# BLDC_Motor_Driver_mb.net
KiCad netlist of a schematic drawn in EAGLE
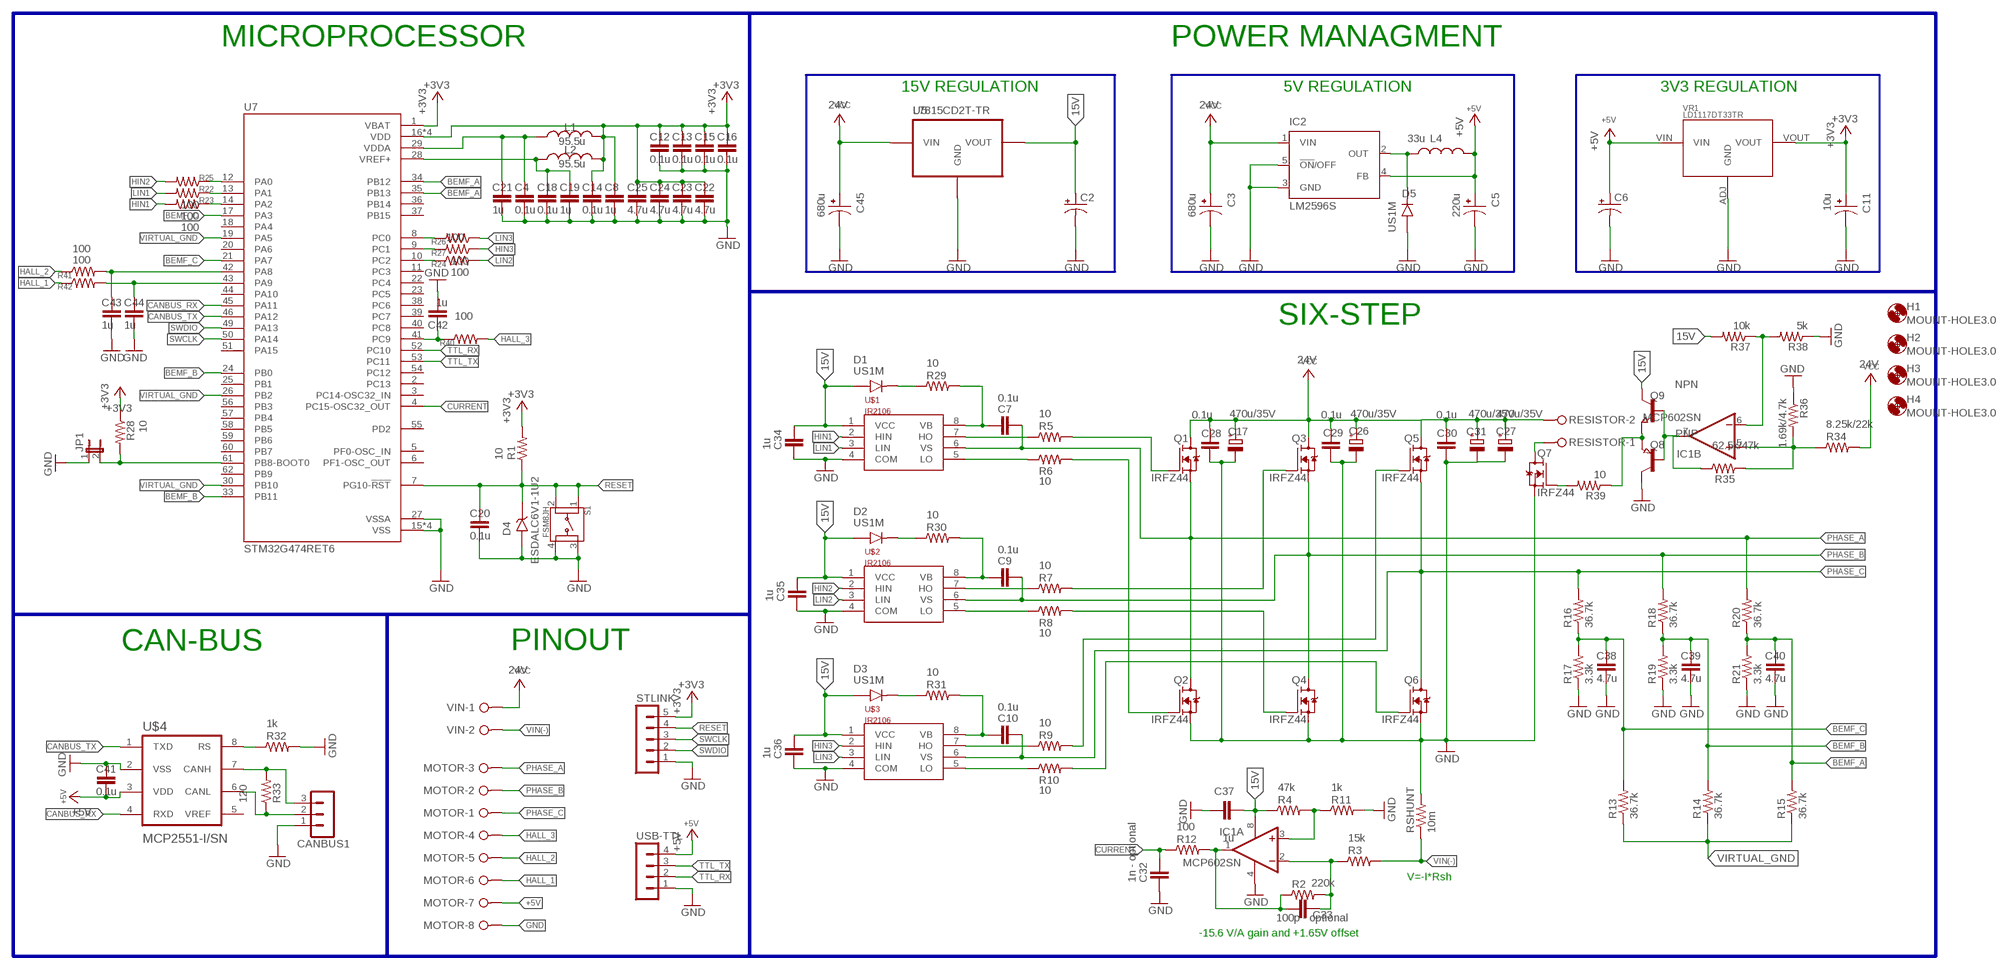
[diagram p0: schematic, sheet 1]

(export (version "E")
  (design (tool "Eeschema 10.0.6"))
  (components
    (comp (ref "C2")
      (value "CPOL-US153CLV-0405")
      (footprint "eagle-import:153CLV-0405")
      (libsource (lib "eagle-import") (part "CPOL-US153CLV-0405"))
    )
    (comp (ref "C3")
      (value "680u")
      (footprint "eagle-import:CAP_EEEFK1H221P")
      (fields (field (name "MF") "Panasonic") (field (name "MP") "EEE-FK1H221P"))
      (libsource (lib "eagle-import") (part "EEEFK1H221P"))
    )
    (comp (ref "C4")
      (value "0.1u")
      (footprint "eagle-import:C1206")
      (libsource (lib "eagle-import") (part "C-EUC1206"))
    )
    (comp (ref "C5")
      (value "220u")
      (footprint "eagle-import:CAP_EEEFK1H221P")
      (fields (field (name "MF") "Panasonic") (field (name "MP") "EEE-FK1H221P"))
      (libsource (lib "eagle-import") (part "EEEFK1H221P"))
    )
    (comp (ref "C6")
      (value "CPOL-US153CLV-0405")
      (footprint "eagle-import:153CLV-0405")
      (libsource (lib "eagle-import") (part "CPOL-US153CLV-0405"))
    )
    (comp (ref "C7")
      (value "0.1u")
      (footprint "eagle-import:C1206")
      (libsource (lib "eagle-import") (part "C-EUC1206"))
    )
    (comp (ref "C8")
      (value "1u")
      (footprint "eagle-import:C1206")
      (libsource (lib "eagle-import") (part "C-EUC1206"))
    )
    (comp (ref "C9")
      (value "0.1u")
      (footprint "eagle-import:C1206")
      (libsource (lib "eagle-import") (part "C-EUC1206"))
    )
    (comp (ref "C10")
      (value "0.1u")
      (footprint "eagle-import:C1206")
      (libsource (lib "eagle-import") (part "C-EUC1206"))
    )
    (comp (ref "C11")
      (value "10u")
      (footprint "eagle-import:CAP_EEEFK1H221P")
      (fields (field (name "MF") "Panasonic") (field (name "MP") "EEE-FK1H221P"))
      (libsource (lib "eagle-import") (part "EEEFK1H221P"))
    )
    (comp (ref "C12")
      (value "0.1u")
      (footprint "eagle-import:C1206")
      (libsource (lib "eagle-import") (part "C-EUC1206"))
    )
    (comp (ref "C13")
      (value "0.1u")
      (footprint "eagle-import:C1206")
      (libsource (lib "eagle-import") (part "C-EUC1206"))
    )
    (comp (ref "C14")
      (value "0.1u")
      (footprint "eagle-import:C1206")
      (libsource (lib "eagle-import") (part "C-EUC1206"))
    )
    (comp (ref "C15")
      (value "0.1u")
      (footprint "eagle-import:C1206")
      (libsource (lib "eagle-import") (part "C-EUC1206"))
    )
    (comp (ref "C16")
      (value "0.1u")
      (footprint "eagle-import:C1206")
      (libsource (lib "eagle-import") (part "C-EUC1206"))
    )
    (comp (ref "C17")
      (value "470u/35V")
      (footprint "eagle-import:E7,5-16")
      (libsource (lib "eagle-import") (part "CPOL-EUE7.5-16"))
    )
    (comp (ref "C18")
      (value "0.1u")
      (footprint "eagle-import:C1206")
      (libsource (lib "eagle-import") (part "C-EUC1206"))
    )
    (comp (ref "C19")
      (value "1u")
      (footprint "eagle-import:C1206")
      (libsource (lib "eagle-import") (part "C-EUC1206"))
    )
    (comp (ref "C20")
      (value "0.1u")
      (footprint "eagle-import:C1206")
      (libsource (lib "eagle-import") (part "C-EUC1206"))
    )
    (comp (ref "C21")
      (value "1u")
      (footprint "eagle-import:C1206")
      (libsource (lib "eagle-import") (part "C-EUC1206"))
    )
    (comp (ref "C22")
      (value "4.7u")
      (footprint "eagle-import:C1206")
      (libsource (lib "eagle-import") (part "C-EUC1206"))
    )
    (comp (ref "C23")
      (value "4.7u")
      (footprint "eagle-import:C1206")
      (libsource (lib "eagle-import") (part "C-EUC1206"))
    )
    (comp (ref "C24")
      (value "4.7u")
      (footprint "eagle-import:C1206")
      (libsource (lib "eagle-import") (part "C-EUC1206"))
    )
    (comp (ref "C25")
      (value "4.7u")
      (footprint "eagle-import:C1206")
      (libsource (lib "eagle-import") (part "C-EUC1206"))
    )
    (comp (ref "C26")
      (value "470u/35V")
      (footprint "eagle-import:E7,5-16")
      (libsource (lib "eagle-import") (part "CPOL-EUE7.5-16"))
    )
    (comp (ref "C27")
      (value "470u/35V")
      (footprint "eagle-import:E7,5-16")
      (libsource (lib "eagle-import") (part "CPOL-EUE7.5-16"))
    )
    (comp (ref "C28")
      (value "0.1u")
      (footprint "eagle-import:C1206")
      (libsource (lib "eagle-import") (part "C-EUC1206"))
    )
    (comp (ref "C29")
      (value "0.1u")
      (footprint "eagle-import:C1206")
      (libsource (lib "eagle-import") (part "C-EUC1206"))
    )
    (comp (ref "C30")
      (value "0.1u")
      (footprint "eagle-import:C1206")
      (libsource (lib "eagle-import") (part "C-EUC1206"))
    )
    (comp (ref "C31")
      (value "470u/35V")
      (footprint "eagle-import:E7,5-16")
      (libsource (lib "eagle-import") (part "CPOL-EUE7.5-16"))
    )
    (comp (ref "C32")
      (value "1n - optional")
      (footprint "eagle-import:C1206")
      (libsource (lib "eagle-import") (part "C-EUC1206"))
    )
    (comp (ref "C33")
      (value "100p - optional")
      (footprint "eagle-import:C1206")
      (libsource (lib "eagle-import") (part "C-EUC1206"))
    )
    (comp (ref "C34")
      (value "1u")
      (footprint "eagle-import:C1206")
      (libsource (lib "eagle-import") (part "C-EUC1206"))
    )
    (comp (ref "C35")
      (value "1u")
      (footprint "eagle-import:C1206")
      (libsource (lib "eagle-import") (part "C-EUC1206"))
    )
    (comp (ref "C36")
      (value "1u")
      (footprint "eagle-import:C1206")
      (libsource (lib "eagle-import") (part "C-EUC1206"))
    )
    (comp (ref "C37")
      (value "1u")
      (footprint "eagle-import:C1206")
      (libsource (lib "eagle-import") (part "C-EUC1206"))
    )
    (comp (ref "C38")
      (value "4.7u")
      (footprint "eagle-import:C1206")
      (libsource (lib "eagle-import") (part "C-EUC1206"))
    )
    (comp (ref "C39")
      (value "4.7u")
      (footprint "eagle-import:C1206")
      (libsource (lib "eagle-import") (part "C-EUC1206"))
    )
    (comp (ref "C40")
      (value "4.7u")
      (footprint "eagle-import:C1206")
      (libsource (lib "eagle-import") (part "C-EUC1206"))
    )
    (comp (ref "C41")
      (value "0.1u")
      (footprint "eagle-import:C1206")
      (libsource (lib "eagle-import") (part "C-EUC1206"))
    )
    (comp (ref "C42")
      (value "1u")
      (footprint "eagle-import:C1206")
      (libsource (lib "eagle-import") (part "C-EUC1206"))
    )
    (comp (ref "C43")
      (value "1u")
      (footprint "eagle-import:C1206")
      (libsource (lib "eagle-import") (part "C-EUC1206"))
    )
    (comp (ref "C44")
      (value "1u")
      (footprint "eagle-import:C1206")
      (libsource (lib "eagle-import") (part "C-EUC1206"))
    )
    (comp (ref "C45")
      (value "680u")
      (footprint "eagle-import:CAP_EEEFK1H221P")
      (fields (field (name "MF") "Panasonic") (field (name "MP") "EEE-FK1H221P"))
      (libsource (lib "eagle-import") (part "EEEFK1H221P"))
    )
    (comp (ref "CANBUS1")
      (value "MA03-1")
      (footprint "eagle-import:MA03-1")
      (libsource (lib "eagle-import") (part "MA03-1"))
    )
    (comp (ref "D1")
      (value "US1M")
      (footprint "eagle-import:DIOM4325X250N")
      (fields (field (name "MF") "Taiwan Semiconductor"))
      (libsource (lib "eagle-import") (part "US1M"))
    )
    (comp (ref "D2")
      (value "US1M")
      (footprint "eagle-import:DIOM4325X250N")
      (fields (field (name "MF") "Taiwan Semiconductor"))
      (libsource (lib "eagle-import") (part "US1M"))
    )
    (comp (ref "D3")
      (value "US1M")
      (footprint "eagle-import:DIOM4325X250N")
      (fields (field (name "MF") "Taiwan Semiconductor"))
      (libsource (lib "eagle-import") (part "US1M"))
    )
    (comp (ref "D4")
      (value "ESDALC6V1-1U2")
      (footprint "eagle-import:DIODE_ESDALC6V1-1U2")
      (fields (field (name "MF") "STMicroelectronics"))
      (libsource (lib "eagle-import") (part "ESDALC6V1-1U2"))
    )
    (comp (ref "D5")
      (value "US1M")
      (footprint "eagle-import:DIOM4325X250N")
      (fields (field (name "MF") "Taiwan Semiconductor"))
      (libsource (lib "eagle-import") (part "US1M"))
    )
    (comp (ref "H1")
      (value "MOUNT-HOLE3.0")
      (footprint "eagle-import:3,0")
      (libsource (lib "eagle-import") (part "MOUNT-HOLE3.0"))
    )
    (comp (ref "H2")
      (value "MOUNT-HOLE3.0")
      (footprint "eagle-import:3,0")
      (libsource (lib "eagle-import") (part "MOUNT-HOLE3.0"))
    )
    (comp (ref "H3")
      (value "MOUNT-HOLE3.0")
      (footprint "eagle-import:3,0")
      (libsource (lib "eagle-import") (part "MOUNT-HOLE3.0"))
    )
    (comp (ref "H4")
      (value "MOUNT-HOLE3.0")
      (footprint "eagle-import:3,0")
      (libsource (lib "eagle-import") (part "MOUNT-HOLE3.0"))
    )
    (comp (ref "IC1")
      (value "MCP602SN")
      (footprint "eagle-import:SO08")
      (libsource (lib "eagle-import") (part "MCP602SN"))
    )
    (comp (ref "IC2")
      (value "LM2596S")
      (footprint "eagle-import:TO263-5")
      (fields (field (name "MF") "NATIONAL SEMICONDUCTOR") (field (name "MPN") "LM2596S-ADJ/NOPB"))
      (libsource (lib "eagle-import") (part "LM2596S"))
    )
    (comp (ref "JP1")
      (value "JP1E")
      (footprint "eagle-import:JP1")
      (libsource (lib "eagle-import") (part "JP1E"))
    )
    (comp (ref "L1")
      (value "95.5u")
      (footprint "eagle-import:L3225P")
      (libsource (lib "eagle-import") (part "L-USL3225P"))
    )
    (comp (ref "L2")
      (value "95.5u")
      (footprint "eagle-import:L3225P")
      (libsource (lib "eagle-import") (part "L-USL3225P"))
    )
    (comp (ref "L4")
      (value "33u")
      (footprint "eagle-import:IHLP4040")
      (libsource (lib "eagle-import") (part "IHLP4040"))
    )
    (comp (ref "MOTOR")
      (value "W237-08P")
      (footprint "eagle-import:W237-8P")
      (libsource (lib "eagle-import") (part "W237-08P"))
    )
    (comp (ref "Q1")
      (value "IRFZ44")
      (footprint "eagle-import:DPAK254P1524X483-3N")
      (fields (field (name "MF") "Infineon Technologies") (field (name "MP") "IRFZ44NSTRRPBF"))
      (libsource (lib "eagle-import") (part "IRFZ44NSTRRPBF"))
    )
    (comp (ref "Q2")
      (value "IRFZ44")
      (footprint "eagle-import:DPAK254P1524X483-3N")
      (fields (field (name "MF") "Infineon Technologies") (field (name "MP") "IRFZ44NSTRRPBF"))
      (libsource (lib "eagle-import") (part "IRFZ44NSTRRPBF"))
    )
    (comp (ref "Q3")
      (value "IRFZ44")
      (footprint "eagle-import:DPAK254P1524X483-3N")
      (fields (field (name "MF") "Infineon Technologies") (field (name "MP") "IRFZ44NSTRRPBF"))
      (libsource (lib "eagle-import") (part "IRFZ44NSTRRPBF"))
    )
    (comp (ref "Q4")
      (value "IRFZ44")
      (footprint "eagle-import:DPAK254P1524X483-3N")
      (fields (field (name "MF") "Infineon Technologies") (field (name "MP") "IRFZ44NSTRRPBF"))
      (libsource (lib "eagle-import") (part "IRFZ44NSTRRPBF"))
    )
    (comp (ref "Q5")
      (value "IRFZ44")
      (footprint "eagle-import:DPAK254P1524X483-3N")
      (fields (field (name "MF") "Infineon Technologies") (field (name "MP") "IRFZ44NSTRRPBF"))
      (libsource (lib "eagle-import") (part "IRFZ44NSTRRPBF"))
    )
    (comp (ref "Q6")
      (value "IRFZ44")
      (footprint "eagle-import:DPAK254P1524X483-3N")
      (fields (field (name "MF") "Infineon Technologies") (field (name "MP") "IRFZ44NSTRRPBF"))
      (libsource (lib "eagle-import") (part "IRFZ44NSTRRPBF"))
    )
    (comp (ref "Q7")
      (value "IRFZ44")
      (footprint "eagle-import:DPAK254P1524X483-3N")
      (fields (field (name "MF") "Infineon Technologies") (field (name "MP") "IRFZ44NSTRRPBF"))
      (libsource (lib "eagle-import") (part "IRFZ44NSTRRPBF"))
    )
    (comp (ref "Q8")
      (value "PNP")
      (footprint "eagle-import:SOT23")
      (libsource (lib "eagle-import") (part "PNP-TRANSISTOR_SOT23"))
    )
    (comp (ref "Q9")
      (value "NPN")
      (footprint "eagle-import:SOT23")
      (libsource (lib "eagle-import") (part "NPN-TRANSISTOR_SOT23"))
    )
    (comp (ref "R1")
      (value "10")
      (footprint "eagle-import:R1206")
      (libsource (lib "eagle-import") (part "R-US_R1206"))
    )
    (comp (ref "R2")
      (value "220k")
      (footprint "eagle-import:R1206")
      (libsource (lib "eagle-import") (part "R-US_R1206"))
    )
    (comp (ref "R3")
      (value "15k")
      (footprint "eagle-import:R1206")
      (libsource (lib "eagle-import") (part "R-US_R1206"))
    )
    (comp (ref "R4")
      (value "47k")
      (footprint "eagle-import:R1206")
      (libsource (lib "eagle-import") (part "R-US_R1206"))
    )
    (comp (ref "R5")
      (value "10")
      (footprint "eagle-import:R1206")
      (libsource (lib "eagle-import") (part "R-US_R1206"))
    )
    (comp (ref "R6")
      (value "10")
      (footprint "eagle-import:R1206")
      (libsource (lib "eagle-import") (part "R-US_R1206"))
    )
    (comp (ref "R7")
      (value "10")
      (footprint "eagle-import:R1206")
      (libsource (lib "eagle-import") (part "R-US_R1206"))
    )
    (comp (ref "R8")
      (value "10")
      (footprint "eagle-import:R1206")
      (libsource (lib "eagle-import") (part "R-US_R1206"))
    )
    (comp (ref "R9")
      (value "10")
      (footprint "eagle-import:R1206")
      (libsource (lib "eagle-import") (part "R-US_R1206"))
    )
    (comp (ref "R10")
      (value "10")
      (footprint "eagle-import:R1206")
      (libsource (lib "eagle-import") (part "R-US_R1206"))
    )
    (comp (ref "R11")
      (value "1k")
      (footprint "eagle-import:R1206")
      (libsource (lib "eagle-import") (part "R-US_R1206"))
    )
    (comp (ref "R12")
      (value "100")
      (footprint "eagle-import:R1206")
      (libsource (lib "eagle-import") (part "R-US_R1206"))
    )
    (comp (ref "R13")
      (value "36.7k")
      (footprint "eagle-import:R1206")
      (libsource (lib "eagle-import") (part "R-US_R1206"))
    )
    (comp (ref "R14")
      (value "36.7k")
      (footprint "eagle-import:R1206")
      (libsource (lib "eagle-import") (part "R-US_R1206"))
    )
    (comp (ref "R15")
      (value "36.7k")
      (footprint "eagle-import:R1206")
      (libsource (lib "eagle-import") (part "R-US_R1206"))
    )
    (comp (ref "R16")
      (value "36.7k")
      (footprint "eagle-import:R1206")
      (libsource (lib "eagle-import") (part "R-US_R1206"))
    )
    (comp (ref "R17")
      (value "3.3k")
      (footprint "eagle-import:R1206")
      (libsource (lib "eagle-import") (part "R-US_R1206"))
    )
    (comp (ref "R18")
      (value "36.7k")
      (footprint "eagle-import:R1206")
      (libsource (lib "eagle-import") (part "R-US_R1206"))
    )
    (comp (ref "R19")
      (value "3.3k")
      (footprint "eagle-import:R1206")
      (libsource (lib "eagle-import") (part "R-US_R1206"))
    )
    (comp (ref "R20")
      (value "36.7k")
      (footprint "eagle-import:R1206")
      (libsource (lib "eagle-import") (part "R-US_R1206"))
    )
    (comp (ref "R21")
      (value "3.3k")
      (footprint "eagle-import:R1206")
      (libsource (lib "eagle-import") (part "R-US_R1206"))
    )
    (comp (ref "R22")
      (value "100")
      (footprint "eagle-import:R1206")
      (libsource (lib "eagle-import") (part "R-US_R1206"))
    )
    (comp (ref "R23")
      (value "100")
      (footprint "eagle-import:R1206")
      (libsource (lib "eagle-import") (part "R-US_R1206"))
    )
    (comp (ref "R24")
      (value "100")
      (footprint "eagle-import:R1206")
      (libsource (lib "eagle-import") (part "R-US_R1206"))
    )
    (comp (ref "R25")
      (value "100")
      (footprint "eagle-import:R1206")
      (libsource (lib "eagle-import") (part "R-US_R1206"))
    )
    (comp (ref "R26")
      (value "100")
      (footprint "eagle-import:R1206")
      (libsource (lib "eagle-import") (part "R-US_R1206"))
    )
    (comp (ref "R27")
      (value "100")
      (footprint "eagle-import:R1206")
      (libsource (lib "eagle-import") (part "R-US_R1206"))
    )
    (comp (ref "R28")
      (value "10")
      (footprint "eagle-import:R1206")
      (libsource (lib "eagle-import") (part "R-US_R1206"))
    )
    (comp (ref "R29")
      (value "10")
      (footprint "eagle-import:R1206")
      (libsource (lib "eagle-import") (part "R-US_R1206"))
    )
    (comp (ref "R30")
      (value "10")
      (footprint "eagle-import:R1206")
      (libsource (lib "eagle-import") (part "R-US_R1206"))
    )
    (comp (ref "R31")
      (value "10")
      (footprint "eagle-import:R1206")
      (libsource (lib "eagle-import") (part "R-US_R1206"))
    )
    (comp (ref "R32")
      (value "1k")
      (footprint "eagle-import:R1206")
      (libsource (lib "eagle-import") (part "R-US_R1206"))
    )
    (comp (ref "R33")
      (value "120")
      (footprint "eagle-import:R1206")
      (libsource (lib "eagle-import") (part "R-US_R1206"))
    )
    (comp (ref "R34")
      (value "8.25k/22k")
      (footprint "eagle-import:R1206")
      (libsource (lib "eagle-import") (part "R-US_R1206"))
    )
    (comp (ref "R35")
      (value "62.5k/47k")
      (footprint "eagle-import:R1206")
      (libsource (lib "eagle-import") (part "R-US_R1206"))
    )
    (comp (ref "R36")
      (value "1.69k/4.7k")
      (footprint "eagle-import:R1206")
      (libsource (lib "eagle-import") (part "R-US_R1206"))
    )
    (comp (ref "R37")
      (value "10k")
      (footprint "eagle-import:R1206")
      (libsource (lib "eagle-import") (part "R-US_R1206"))
    )
    (comp (ref "R38")
      (value "5k")
      (footprint "eagle-import:R1206")
      (libsource (lib "eagle-import") (part "R-US_R1206"))
    )
    (comp (ref "R39")
      (value "10")
      (footprint "eagle-import:R1206")
      (libsource (lib "eagle-import") (part "R-US_R1206"))
    )
    (comp (ref "R40")
      (value "100")
      (footprint "eagle-import:R1206")
      (libsource (lib "eagle-import") (part "R-US_R1206"))
    )
    (comp (ref "R41")
      (value "100")
      (footprint "eagle-import:R1206")
      (libsource (lib "eagle-import") (part "R-US_R1206"))
    )
    (comp (ref "R42")
      (value "100")
      (footprint "eagle-import:R1206")
      (libsource (lib "eagle-import") (part "R-US_R1206"))
    )
    (comp (ref "RESISTOR")
      (value "W237-02P")
      (footprint "eagle-import:W237-132")
      (libsource (lib "eagle-import") (part "W237-02P"))
    )
    (comp (ref "RSHUNT")
      (value "10m")
      (footprint "eagle-import:R1210")
      (libsource (lib "eagle-import") (part "R-US_R1210"))
    )
    (comp (ref "S1")
      (value "FSM8JH")
      (footprint "eagle-import:SW_FSM8JH")
      (fields (field (name "MF") "TE Connectivity"))
      (libsource (lib "eagle-import") (part "FSM8JH"))
    )
    (comp (ref "STLINK")
      (value "MA05-1")
      (footprint "eagle-import:MA05-1")
      (libsource (lib "eagle-import") (part "MA05-1"))
    )
    (comp (ref "U$1")
      (value "IR2106")
      (footprint "eagle-import:SOIC-8")
      (libsource (lib "eagle-import") (part "IR2106"))
    )
    (comp (ref "U$2")
      (value "IR2106")
      (footprint "eagle-import:SOIC-8")
      (libsource (lib "eagle-import") (part "IR2106"))
    )
    (comp (ref "U$3")
      (value "IR2106")
      (footprint "eagle-import:SOIC-8")
      (libsource (lib "eagle-import") (part "IR2106"))
    )
    (comp (ref "U$4")
      (value "MCP2551-I/SN")
      (footprint "eagle-import:SOIC127P599X175-8N")
      (fields (field (name "MF") "Microchip"))
      (libsource (lib "eagle-import") (part "MCP2551-I/SN"))
    )
    (comp (ref "U5")
      (value "L7815CD2T-TR")
      (footprint "eagle-import:D2PAK")
      (fields (field (name "MF") "STMicroelectronics"))
      (libsource (lib "eagle-import") (part "L7815CD2T-TR"))
    )
    (comp (ref "U7")
      (value "STM32G474RET6")
      (footprint "eagle-import:QFP50P1200X1200X160-64N")
      (fields
        (field (name "DIGIKEY_PART_NUMBER") "497-STM32G474RET6-ND")
        (field (name "MF") "STMicroelectronics")
      )
      (libsource (lib "eagle-import") (part "STM32G474RET6"))
    )
    (comp (ref "USB-TTL")
      (value "MA04-1")
      (footprint "eagle-import:MA04-1")
      (libsource (lib "eagle-import") (part "MA04-1"))
    )
    (comp (ref "VIN")
      (value "W237-02P")
      (footprint "eagle-import:W237-132")
      (libsource (lib "eagle-import") (part "W237-02P"))
    )
    (comp (ref "VR1")
      (value "LD1117DT33TR")
      (footprint "eagle-import:DPAK456P1010X240-3N")
      (fields (field (name "MF") "STMicroelectronics"))
      (libsource (lib "eagle-import") (part "LD1117DT33TR"))
    )
  )
  (nets
    (net (code "2") (name "+3V3") (class "Default")
      (node (ref "C11") (pin "1") (pinfunction "1_1") (pintype "passive"))
      (node (ref "C12") (pin "1") (pinfunction "1_1") (pintype "passive"))
      (node (ref "C13") (pin "1") (pinfunction "1_1") (pintype "passive"))
      (node (ref "C14") (pin "1") (pinfunction "1_1") (pintype "passive"))
      (node (ref "C15") (pin "1") (pinfunction "1_1") (pintype "passive"))
      (node (ref "C16") (pin "1") (pinfunction "1_1") (pintype "passive"))
      (node (ref "C22") (pin "1") (pinfunction "1_1") (pintype "passive"))
      (node (ref "C23") (pin "1") (pinfunction "1_1") (pintype "passive"))
      (node (ref "C24") (pin "1") (pinfunction "1_1") (pintype "passive"))
      (node (ref "C25") (pin "1") (pinfunction "1_1") (pintype "passive"))
      (node (ref "C8") (pin "1") (pinfunction "1_1") (pintype "passive"))
      (node (ref "L1") (pin "2") (pinfunction "2_2") (pintype "passive"))
      (node (ref "L2") (pin "2") (pinfunction "2_2") (pintype "passive"))
      (node (ref "R1") (pin "2") (pinfunction "2_2") (pintype "passive"))
      (node (ref "R28") (pin "1") (pinfunction "1_1") (pintype "passive"))
      (node (ref "STLINK") (pin "5") (pinfunction "5_5") (pintype "passive"))
      (node (ref "U7") (pin "1") (pinfunction "VBAT_1") (pintype "power_in"))
      (node (ref "U7") (pin "16") (pinfunction "VDD_16") (pintype "power_in"))
      (node (ref "U7") (pin "32") (pinfunction "VDD_32") (pintype "power_in"))
      (node (ref "U7") (pin "48") (pinfunction "VDD_48") (pintype "power_in"))
      (node (ref "U7") (pin "64") (pinfunction "VDD_64") (pintype "power_in"))
      (node (ref "VR1") (pin "VOUT") (pinfunction "VOUT_VOUT") (pintype "output"))
    )
    (net (code "3") (name "+5V") (class "Default")
      (node (ref "C41") (pin "2") (pinfunction "2_2") (pintype "passive"))
      (node (ref "C5") (pin "1") (pinfunction "1_1") (pintype "passive"))
      (node (ref "C6") (pin "+") (pinfunction "+_+") (pintype "passive"))
      (node (ref "IC2") (pin "4") (pinfunction "FB_4") (pintype "input"))
      (node (ref "L4") (pin "2") (pinfunction "2_2") (pintype "passive"))
      (node (ref "MOTOR") (pin "7") (pinfunction "KL_7") (pintype "passive"))
      (node (ref "U$4") (pin "3") (pinfunction "VDD_3") (pintype "power_in"))
      (node (ref "USB-TTL") (pin "4") (pinfunction "4_4") (pintype "passive"))
      (node (ref "VR1") (pin "VIN") (pinfunction "VIN_VIN") (pintype "input"))
    )
    (net (code "5") (name "15V") (class "Default")
      (node (ref "C2") (pin "+") (pinfunction "+_+") (pintype "passive"))
      (node (ref "C34") (pin "2") (pinfunction "2_2") (pintype "passive"))
      (node (ref "C35") (pin "2") (pinfunction "2_2") (pintype "passive"))
      (node (ref "C36") (pin "2") (pinfunction "2_2") (pintype "passive"))
      (node (ref "C37") (pin "1") (pinfunction "1_1") (pintype "passive"))
      (node (ref "D1") (pin "A") (pinfunction "A_A") (pintype "passive"))
      (node (ref "D2") (pin "A") (pinfunction "A_A") (pintype "passive"))
      (node (ref "D3") (pin "A") (pinfunction "A_A") (pintype "passive"))
      (node (ref "IC1") (pin "8") (pinfunction "V+_8") (pintype "power_in"))
      (node (ref "Q9") (pin "3") (pinfunction "C_3") (pintype "passive"))
      (node (ref "R37") (pin "2") (pinfunction "2_2") (pintype "passive"))
      (node (ref "R4") (pin "1") (pinfunction "1_1") (pintype "passive"))
      (node (ref "U$1") (pin "1") (pinfunction "VCC_1") (pintype "bidirectional"))
      (node (ref "U$2") (pin "1") (pinfunction "VCC_1") (pintype "bidirectional"))
      (node (ref "U$3") (pin "1") (pinfunction "VCC_1") (pintype "bidirectional"))
      (node (ref "U5") (pin "VOUT") (pinfunction "VOUT_VOUT") (pintype "bidirectional"))
    )
    (net (code "6") (name "24V") (class "Default")
      (node (ref "C17") (pin "+") (pinfunction "+_+") (pintype "passive"))
      (node (ref "C26") (pin "+") (pinfunction "+_+") (pintype "passive"))
      (node (ref "C27") (pin "+") (pinfunction "+_+") (pintype "passive"))
      (node (ref "C28") (pin "1") (pinfunction "1_1") (pintype "passive"))
      (node (ref "C29") (pin "1") (pinfunction "1_1") (pintype "passive"))
      (node (ref "C3") (pin "1") (pinfunction "1_1") (pintype "passive"))
      (node (ref "C30") (pin "1") (pinfunction "1_1") (pintype "passive"))
      (node (ref "C31") (pin "+") (pinfunction "+_+") (pintype "passive"))
      (node (ref "C45") (pin "1") (pinfunction "1_1") (pintype "passive"))
      (node (ref "IC2") (pin "1") (pinfunction "VIN_1") (pintype "input"))
      (node (ref "Q1") (pin "2") (pinfunction "D_2") (pintype "passive"))
      (node (ref "Q3") (pin "2") (pinfunction "D_2") (pintype "passive"))
      (node (ref "Q5") (pin "2") (pinfunction "D_2") (pintype "passive"))
      (node (ref "R34") (pin "2") (pinfunction "2_2") (pintype "passive"))
      (node (ref "RESISTOR") (pin "2") (pinfunction "KL_2") (pintype "passive"))
      (node (ref "U5") (pin "VIN") (pinfunction "VIN_VIN") (pintype "bidirectional"))
      (node (ref "VIN") (pin "1") (pinfunction "KL_1") (pintype "passive"))
    )
    (net (code "7") (name "BEMF_A") (class "Default")
      (node (ref "C40") (pin "1") (pinfunction "1_1") (pintype "passive"))
      (node (ref "R15") (pin "2") (pinfunction "2_2") (pintype "passive"))
      (node (ref "R20") (pin "1") (pinfunction "1_1") (pintype "passive"))
      (node (ref "R21") (pin "2") (pinfunction "2_2") (pintype "passive"))
      (node (ref "U7") (pin "34") (pinfunction "PB12_34") (pintype "bidirectional"))
      (node (ref "U7") (pin "35") (pinfunction "PB13_35") (pintype "bidirectional"))
    )
    (net (code "8") (name "BEMF_B") (class "Default")
      (node (ref "C39") (pin "1") (pinfunction "1_1") (pintype "passive"))
      (node (ref "R14") (pin "2") (pinfunction "2_2") (pintype "passive"))
      (node (ref "R18") (pin "1") (pinfunction "1_1") (pintype "passive"))
      (node (ref "R19") (pin "2") (pinfunction "2_2") (pintype "passive"))
      (node (ref "U7") (pin "24") (pinfunction "PB0_24") (pintype "bidirectional"))
      (node (ref "U7") (pin "33") (pinfunction "PB11_33") (pintype "bidirectional"))
    )
    (net (code "9") (name "BEMF_C") (class "Default")
      (node (ref "C38") (pin "1") (pinfunction "1_1") (pintype "passive"))
      (node (ref "R13") (pin "2") (pinfunction "2_2") (pintype "passive"))
      (node (ref "R16") (pin "1") (pinfunction "1_1") (pintype "passive"))
      (node (ref "R17") (pin "2") (pinfunction "2_2") (pintype "passive"))
      (node (ref "U7") (pin "17") (pinfunction "PA3_17") (pintype "bidirectional"))
      (node (ref "U7") (pin "21") (pinfunction "PA7_21") (pintype "bidirectional"))
    )
    (net (code "10") (name "CANBUS_RX") (class "Default")
      (node (ref "U$4") (pin "4") (pinfunction "RXD_4") (pintype "output"))
      (node (ref "U7") (pin "45") (pinfunction "PA11_45") (pintype "bidirectional"))
    )
    (net (code "11") (name "CANBUS_TX") (class "Default")
      (node (ref "U$4") (pin "1") (pinfunction "TXD_1") (pintype "input"))
      (node (ref "U7") (pin "46") (pinfunction "PA12_46") (pintype "bidirectional"))
    )
    (net (code "12") (name "CURRENT") (class "Default")
      (node (ref "C32") (pin "2") (pinfunction "2_2") (pintype "passive"))
      (node (ref "R12") (pin "1") (pinfunction "1_1") (pintype "passive"))
      (node (ref "U7") (pin "4") (pinfunction "PC15-OSC32_OUT_4") (pintype "bidirectional"))
    )
    (net (code "13") (name "GND") (class "Default")
      (node (ref "C11") (pin "2") (pinfunction "2_2") (pintype "passive"))
      (node (ref "C12") (pin "2") (pinfunction "2_2") (pintype "passive"))
      (node (ref "C13") (pin "2") (pinfunction "2_2") (pintype "passive"))
      (node (ref "C14") (pin "2") (pinfunction "2_2") (pintype "passive"))
      (node (ref "C15") (pin "2") (pinfunction "2_2") (pintype "passive"))
      (node (ref "C16") (pin "2") (pinfunction "2_2") (pintype "passive"))
      (node (ref "C17") (pin "-") (pinfunction "-_-") (pintype "passive"))
      (node (ref "C18") (pin "2") (pinfunction "2_2") (pintype "passive"))
      (node (ref "C19") (pin "2") (pinfunction "2_2") (pintype "passive"))
      (node (ref "C2") (pin "-") (pinfunction "-_-") (pintype "passive"))
      (node (ref "C20") (pin "2") (pinfunction "2_2") (pintype "passive"))
      (node (ref "C21") (pin "2") (pinfunction "2_2") (pintype "passive"))
      (node (ref "C22") (pin "2") (pinfunction "2_2") (pintype "passive"))
      (node (ref "C23") (pin "2") (pinfunction "2_2") (pintype "passive"))
      (node (ref "C24") (pin "2") (pinfunction "2_2") (pintype "passive"))
      (node (ref "C25") (pin "2") (pinfunction "2_2") (pintype "passive"))
      (node (ref "C26") (pin "-") (pinfunction "-_-") (pintype "passive"))
      (node (ref "C27") (pin "-") (pinfunction "-_-") (pintype "passive"))
      (node (ref "C28") (pin "2") (pinfunction "2_2") (pintype "passive"))
      (node (ref "C29") (pin "2") (pinfunction "2_2") (pintype "passive"))
      (node (ref "C3") (pin "2") (pinfunction "2_2") (pintype "passive"))
      (node (ref "C30") (pin "2") (pinfunction "2_2") (pintype "passive"))
      (node (ref "C31") (pin "-") (pinfunction "-_-") (pintype "passive"))
      (node (ref "C32") (pin "1") (pinfunction "1_1") (pintype "passive"))
      (node (ref "C34") (pin "1") (pinfunction "1_1") (pintype "passive"))
      (node (ref "C35") (pin "1") (pinfunction "1_1") (pintype "passive"))
      (node (ref "C36") (pin "1") (pinfunction "1_1") (pintype "passive"))
      (node (ref "C37") (pin "2") (pinfunction "2_2") (pintype "passive"))
      (node (ref "C38") (pin "2") (pinfunction "2_2") (pintype "passive"))
      (node (ref "C39") (pin "2") (pinfunction "2_2") (pintype "passive"))
      (node (ref "C4") (pin "2") (pinfunction "2_2") (pintype "passive"))
      (node (ref "C40") (pin "2") (pinfunction "2_2") (pintype "passive"))
      (node (ref "C41") (pin "1") (pinfunction "1_1") (pintype "passive"))
      (node (ref "C42") (pin "2") (pinfunction "2_2") (pintype "passive"))
      (node (ref "C43") (pin "2") (pinfunction "2_2") (pintype "passive"))
      (node (ref "C44") (pin "2") (pinfunction "2_2") (pintype "passive"))
      (node (ref "C45") (pin "2") (pinfunction "2_2") (pintype "passive"))
      (node (ref "C5") (pin "2") (pinfunction "2_2") (pintype "passive"))
      (node (ref "C6") (pin "-") (pinfunction "-_-") (pintype "passive"))
      (node (ref "C8") (pin "2") (pinfunction "2_2") (pintype "passive"))
      (node (ref "CANBUS1") (pin "1") (pinfunction "1_1") (pintype "passive"))
      (node (ref "D4") (pin "2") (pinfunction "A_2") (pintype "passive"))
      (node (ref "D5") (pin "A") (pinfunction "A_A") (pintype "passive"))
      (node (ref "IC1") (pin "4") (pinfunction "V-_4") (pintype "power_in"))
      (node (ref "IC2") (pin "3") (pinfunction "GND_3") (pintype "power_in"))
      (node (ref "IC2") (pin "5") (pinfunction "~{ON}/OFF_5") (pintype "input"))
      (node (ref "JP1") (pin "1") (pinfunction "1_1") (pintype "passive"))
      (node (ref "MOTOR") (pin "8") (pinfunction "KL_8") (pintype "passive"))
      (node (ref "Q2") (pin "3") (pinfunction "S_3") (pintype "passive"))
      (node (ref "Q4") (pin "3") (pinfunction "S_3") (pintype "passive"))
      (node (ref "Q6") (pin "3") (pinfunction "S_3") (pintype "passive"))
      (node (ref "Q7") (pin "3") (pinfunction "S_3") (pintype "passive"))
      (node (ref "Q8") (pin "3") (pinfunction "C_3") (pintype "passive"))
      (node (ref "R11") (pin "2") (pinfunction "2_2") (pintype "passive"))
      (node (ref "R17") (pin "1") (pinfunction "1_1") (pintype "passive"))
      (node (ref "R19") (pin "1") (pinfunction "1_1") (pintype "passive"))
      (node (ref "R21") (pin "1") (pinfunction "1_1") (pintype "passive"))
      (node (ref "R32") (pin "2") (pinfunction "2_2") (pintype "passive"))
      (node (ref "R36") (pin "1") (pinfunction "1_1") (pintype "passive"))
      (node (ref "R38") (pin "1") (pinfunction "1_1") (pintype "passive"))
      (node (ref "RSHUNT") (pin "2") (pinfunction "2_2") (pintype "passive"))
      (node (ref "S1") (pin "3") (pinfunction "3_3") (pintype "passive"))
      (node (ref "S1") (pin "4") (pinfunction "4_4") (pintype "passive"))
      (node (ref "STLINK") (pin "1") (pinfunction "1_1") (pintype "passive"))
      (node (ref "U$1") (pin "4") (pinfunction "COM_4") (pintype "bidirectional"))
      (node (ref "U$2") (pin "4") (pinfunction "COM_4") (pintype "bidirectional"))
      (node (ref "U$3") (pin "4") (pinfunction "COM_4") (pintype "bidirectional"))
      (node (ref "U$4") (pin "2") (pinfunction "VSS_2") (pintype "power_in"))
      (node (ref "U5") (pin "GND") (pinfunction "GND_GND") (pintype "bidirectional"))
      (node (ref "U7") (pin "15") (pinfunction "VSS_15") (pintype "power_in"))
      (node (ref "U7") (pin "27") (pinfunction "VSSA_27") (pintype "power_in"))
      (node (ref "U7") (pin "31") (pinfunction "VSS_31") (pintype "power_in"))
      (node (ref "U7") (pin "47") (pinfunction "VSS_47") (pintype "power_in"))
      (node (ref "U7") (pin "63") (pinfunction "VSS_63") (pintype "power_in"))
      (node (ref "USB-TTL") (pin "1") (pinfunction "1_1") (pintype "passive"))
      (node (ref "VR1") (pin "ADJ") (pinfunction "GND_ADJ") (pintype "power_in"))
    )
    (net (code "14") (name "HALL_1") (class "Default")
      (node (ref "MOTOR") (pin "6") (pinfunction "KL_6") (pintype "passive"))
      (node (ref "R42") (pin "1") (pinfunction "1_1") (pintype "passive"))
    )
    (net (code "15") (name "HALL_2") (class "Default")
      (node (ref "MOTOR") (pin "5") (pinfunction "KL_5") (pintype "passive"))
      (node (ref "R41") (pin "1") (pinfunction "1_1") (pintype "passive"))
    )
    (net (code "16") (name "HALL_3") (class "Default")
      (node (ref "MOTOR") (pin "4") (pinfunction "KL_4") (pintype "passive"))
      (node (ref "R40") (pin "2") (pinfunction "2_2") (pintype "passive"))
    )
    (net (code "17") (name "HIN1") (class "Default")
      (node (ref "R23") (pin "2") (pinfunction "2_2") (pintype "passive"))
      (node (ref "U$1") (pin "2") (pinfunction "HIN_2") (pintype "bidirectional"))
    )
    (net (code "18") (name "HIN2") (class "Default")
      (node (ref "R25") (pin "2") (pinfunction "2_2") (pintype "passive"))
      (node (ref "U$2") (pin "2") (pinfunction "HIN_2") (pintype "bidirectional"))
    )
    (net (code "19") (name "HIN3") (class "Default")
      (node (ref "R27") (pin "1") (pinfunction "1_1") (pintype "passive"))
      (node (ref "U$3") (pin "2") (pinfunction "HIN_2") (pintype "bidirectional"))
    )
    (net (code "20") (name "LIN1") (class "Default")
      (node (ref "R22") (pin "2") (pinfunction "2_2") (pintype "passive"))
      (node (ref "U$1") (pin "3") (pinfunction "LIN_3") (pintype "bidirectional"))
    )
    (net (code "21") (name "LIN2") (class "Default")
      (node (ref "R24") (pin "2") (pinfunction "2_2") (pintype "passive"))
      (node (ref "U$2") (pin "3") (pinfunction "LIN_3") (pintype "bidirectional"))
    )
    (net (code "22") (name "LIN3") (class "Default")
      (node (ref "R26") (pin "1") (pinfunction "1_1") (pintype "passive"))
      (node (ref "U$3") (pin "3") (pinfunction "LIN_3") (pintype "bidirectional"))
    )
    (net (code "23") (name "Net-(D1-K)") (class "Default")
      (node (ref "D1") (pin "C") (pinfunction "K_C") (pintype "passive"))
      (node (ref "R29") (pin "1") (pinfunction "1_1") (pintype "passive"))
    )
    (net (code "24") (name "Net-(D2-K)") (class "Default")
      (node (ref "D2") (pin "C") (pinfunction "K_C") (pintype "passive"))
      (node (ref "R30") (pin "1") (pinfunction "1_1") (pintype "passive"))
    )
    (net (code "25") (name "Net-(D3-K)") (class "Default")
      (node (ref "D3") (pin "C") (pinfunction "K_C") (pintype "passive"))
      (node (ref "R31") (pin "1") (pinfunction "1_1") (pintype "passive"))
    )
    (net (code "26") (name "Net-(D5-K)") (class "Default")
      (node (ref "D5") (pin "C") (pinfunction "K_C") (pintype "passive"))
      (node (ref "IC2") (pin "2") (pinfunction "OUT_2") (pintype "output"))
      (node (ref "L4") (pin "1") (pinfunction "1_1") (pintype "passive"))
    )
    (net (code "27") (name "Net-(IC1A-+IN)") (class "Default")
      (node (ref "IC1") (pin "3") (pinfunction "+IN_3") (pintype "input"))
      (node (ref "R11") (pin "1") (pinfunction "1_1") (pintype "passive"))
      (node (ref "R4") (pin "2") (pinfunction "2_2") (pintype "passive"))
    )
    (net (code "28") (name "Net-(IC1A--IN)") (class "Default")
      (node (ref "C33") (pin "1") (pinfunction "1_1") (pintype "passive"))
      (node (ref "IC1") (pin "2") (pinfunction "-IN_2") (pintype "input"))
      (node (ref "R2") (pin "2") (pinfunction "2_2") (pintype "passive"))
      (node (ref "R3") (pin "1") (pinfunction "1_1") (pintype "passive"))
    )
    (net (code "29") (name "Net-(IC1A-OUT)") (class "Default")
      (node (ref "C33") (pin "2") (pinfunction "2_2") (pintype "passive"))
      (node (ref "IC1") (pin "1") (pinfunction "OUT_1") (pintype "output"))
      (node (ref "R12") (pin "2") (pinfunction "2_2") (pintype "passive"))
      (node (ref "R2") (pin "1") (pinfunction "1_1") (pintype "passive"))
    )
    (net (code "30") (name "Net-(IC1B-+IN)") (class "Default")
      (node (ref "IC1") (pin "5") (pinfunction "+IN_5") (pintype "input"))
      (node (ref "R34") (pin "1") (pinfunction "1_1") (pintype "passive"))
      (node (ref "R35") (pin "2") (pinfunction "2_2") (pintype "passive"))
      (node (ref "R36") (pin "2") (pinfunction "2_2") (pintype "passive"))
    )
    (net (code "31") (name "Net-(IC1B--IN)") (class "Default")
      (node (ref "IC1") (pin "6") (pinfunction "-IN_6") (pintype "input"))
      (node (ref "R37") (pin "1") (pinfunction "1_1") (pintype "passive"))
      (node (ref "R38") (pin "2") (pinfunction "2_2") (pintype "passive"))
    )
    (net (code "32") (name "Net-(IC1B-OUT)") (class "Default")
      (node (ref "IC1") (pin "7") (pinfunction "OUT_7") (pintype "output"))
      (node (ref "Q8") (pin "1") (pinfunction "B_1") (pintype "passive"))
      (node (ref "Q9") (pin "1") (pinfunction "B_1") (pintype "passive"))
      (node (ref "R35") (pin "1") (pinfunction "1_1") (pintype "passive"))
    )
    (net (code "33") (name "Net-(Q1-G)") (class "Default")
      (node (ref "Q1") (pin "1") (pinfunction "G_1") (pintype "passive"))
      (node (ref "R5") (pin "2") (pinfunction "2_2") (pintype "passive"))
    )
    (net (code "34") (name "Net-(Q2-G)") (class "Default")
      (node (ref "Q2") (pin "1") (pinfunction "G_1") (pintype "passive"))
      (node (ref "R6") (pin "2") (pinfunction "2_2") (pintype "passive"))
    )
    (net (code "35") (name "Net-(Q3-G)") (class "Default")
      (node (ref "Q3") (pin "1") (pinfunction "G_1") (pintype "passive"))
      (node (ref "R7") (pin "2") (pinfunction "2_2") (pintype "passive"))
    )
    (net (code "36") (name "Net-(Q4-G)") (class "Default")
      (node (ref "Q4") (pin "1") (pinfunction "G_1") (pintype "passive"))
      (node (ref "R8") (pin "2") (pinfunction "2_2") (pintype "passive"))
    )
    (net (code "37") (name "Net-(Q5-G)") (class "Default")
      (node (ref "Q5") (pin "1") (pinfunction "G_1") (pintype "passive"))
      (node (ref "R9") (pin "2") (pinfunction "2_2") (pintype "passive"))
    )
    (net (code "38") (name "Net-(Q6-G)") (class "Default")
      (node (ref "Q6") (pin "1") (pinfunction "G_1") (pintype "passive"))
      (node (ref "R10") (pin "2") (pinfunction "2_2") (pintype "passive"))
    )
    (net (code "39") (name "Net-(Q7-D)") (class "Default")
      (node (ref "Q7") (pin "2") (pinfunction "D_2") (pintype "passive"))
      (node (ref "RESISTOR") (pin "1") (pinfunction "KL_1") (pintype "passive"))
    )
    (net (code "40") (name "Net-(Q7-G)") (class "Default")
      (node (ref "Q7") (pin "1") (pinfunction "G_1") (pintype "passive"))
      (node (ref "R39") (pin "2") (pinfunction "2_2") (pintype "passive"))
    )
    (net (code "41") (name "Net-(Q8-E)") (class "Default")
      (node (ref "Q8") (pin "2") (pinfunction "E_2") (pintype "passive"))
      (node (ref "Q9") (pin "2") (pinfunction "E_2") (pintype "passive"))
      (node (ref "R39") (pin "1") (pinfunction "1_1") (pintype "passive"))
    )
    (net (code "42") (name "Net-(U$1-HO)") (class "Default")
      (node (ref "R5") (pin "1") (pinfunction "1_1") (pintype "passive"))
      (node (ref "U$1") (pin "7") (pinfunction "HO_7") (pintype "bidirectional"))
    )
    (net (code "43") (name "Net-(U$1-LO)") (class "Default")
      (node (ref "R6") (pin "1") (pinfunction "1_1") (pintype "passive"))
      (node (ref "U$1") (pin "5") (pinfunction "LO_5") (pintype "bidirectional"))
    )
    (net (code "44") (name "Net-(U$1-VB)") (class "Default")
      (node (ref "C7") (pin "1") (pinfunction "1_1") (pintype "passive"))
      (node (ref "R29") (pin "2") (pinfunction "2_2") (pintype "passive"))
      (node (ref "U$1") (pin "8") (pinfunction "VB_8") (pintype "bidirectional"))
    )
    (net (code "45") (name "Net-(U$2-HO)") (class "Default")
      (node (ref "R7") (pin "1") (pinfunction "1_1") (pintype "passive"))
      (node (ref "U$2") (pin "7") (pinfunction "HO_7") (pintype "bidirectional"))
    )
    (net (code "46") (name "Net-(U$2-LO)") (class "Default")
      (node (ref "R8") (pin "1") (pinfunction "1_1") (pintype "passive"))
      (node (ref "U$2") (pin "5") (pinfunction "LO_5") (pintype "bidirectional"))
    )
    (net (code "47") (name "Net-(U$2-VB)") (class "Default")
      (node (ref "C9") (pin "1") (pinfunction "1_1") (pintype "passive"))
      (node (ref "R30") (pin "2") (pinfunction "2_2") (pintype "passive"))
      (node (ref "U$2") (pin "8") (pinfunction "VB_8") (pintype "bidirectional"))
    )
    (net (code "48") (name "Net-(U$3-HO)") (class "Default")
      (node (ref "R9") (pin "1") (pinfunction "1_1") (pintype "passive"))
      (node (ref "U$3") (pin "7") (pinfunction "HO_7") (pintype "bidirectional"))
    )
    (net (code "49") (name "Net-(U$3-LO)") (class "Default")
      (node (ref "R10") (pin "1") (pinfunction "1_1") (pintype "passive"))
      (node (ref "U$3") (pin "5") (pinfunction "LO_5") (pintype "bidirectional"))
    )
    (net (code "50") (name "Net-(U$3-VB)") (class "Default")
      (node (ref "C10") (pin "1") (pinfunction "1_1") (pintype "passive"))
      (node (ref "R31") (pin "2") (pinfunction "2_2") (pintype "passive"))
      (node (ref "U$3") (pin "8") (pinfunction "VB_8") (pintype "bidirectional"))
    )
    (net (code "51") (name "Net-(U$4-CANH)") (class "Default")
      (node (ref "CANBUS1") (pin "3") (pinfunction "3_3") (pintype "passive"))
      (node (ref "R33") (pin "2") (pinfunction "2_2") (pintype "passive"))
      (node (ref "U$4") (pin "7") (pinfunction "CANH_7") (pintype "bidirectional"))
    )
    (net (code "52") (name "Net-(U$4-CANL)") (class "Default")
      (node (ref "CANBUS1") (pin "2") (pinfunction "2_2") (pintype "passive"))
      (node (ref "R33") (pin "1") (pinfunction "1_1") (pintype "passive"))
      (node (ref "U$4") (pin "6") (pinfunction "CANL_6") (pintype "bidirectional"))
    )
    (net (code "53") (name "Net-(U$4-RS)") (class "Default")
      (node (ref "R32") (pin "1") (pinfunction "1_1") (pintype "passive"))
      (node (ref "U$4") (pin "8") (pinfunction "RS_8") (pintype "input"))
    )
    (net (code "54") (name "Net-(U7-PA0)") (class "Default")
      (node (ref "R25") (pin "1") (pinfunction "1_1") (pintype "passive"))
      (node (ref "U7") (pin "12") (pinfunction "PA0_12") (pintype "bidirectional"))
    )
    (net (code "55") (name "Net-(U7-PA1)") (class "Default")
      (node (ref "R22") (pin "1") (pinfunction "1_1") (pintype "passive"))
      (node (ref "U7") (pin "13") (pinfunction "PA1_13") (pintype "bidirectional"))
    )
    (net (code "56") (name "Net-(U7-PA2)") (class "Default")
      (node (ref "R23") (pin "1") (pinfunction "1_1") (pintype "passive"))
      (node (ref "U7") (pin "14") (pinfunction "PA2_14") (pintype "bidirectional"))
    )
    (net (code "57") (name "Net-(U7-PA8)") (class "Default")
      (node (ref "C43") (pin "1") (pinfunction "1_1") (pintype "passive"))
      (node (ref "R41") (pin "2") (pinfunction "2_2") (pintype "passive"))
      (node (ref "U7") (pin "42") (pinfunction "PA8_42") (pintype "bidirectional"))
    )
    (net (code "58") (name "Net-(U7-PA9)") (class "Default")
      (node (ref "C44") (pin "1") (pinfunction "1_1") (pintype "passive"))
      (node (ref "R42") (pin "2") (pinfunction "2_2") (pintype "passive"))
      (node (ref "U7") (pin "43") (pinfunction "PA9_43") (pintype "bidirectional"))
    )
    (net (code "59") (name "Net-(U7-PB8-BOOT0)") (class "Default")
      (node (ref "JP1") (pin "2") (pinfunction "2_2") (pintype "passive"))
      (node (ref "R28") (pin "2") (pinfunction "2_2") (pintype "passive"))
      (node (ref "U7") (pin "61") (pinfunction "PB8-BOOT0_61") (pintype "bidirectional"))
    )
    (net (code "60") (name "Net-(U7-PC0)") (class "Default")
      (node (ref "R26") (pin "2") (pinfunction "2_2") (pintype "passive"))
      (node (ref "U7") (pin "8") (pinfunction "PC0_8") (pintype "bidirectional"))
    )
    (net (code "61") (name "Net-(U7-PC1)") (class "Default")
      (node (ref "R27") (pin "2") (pinfunction "2_2") (pintype "passive"))
      (node (ref "U7") (pin "9") (pinfunction "PC1_9") (pintype "bidirectional"))
    )
    (net (code "62") (name "Net-(U7-PC2)") (class "Default")
      (node (ref "R24") (pin "1") (pinfunction "1_1") (pintype "passive"))
      (node (ref "U7") (pin "10") (pinfunction "PC2_10") (pintype "bidirectional"))
    )
    (net (code "63") (name "Net-(U7-PC9)") (class "Default")
      (node (ref "C42") (pin "1") (pinfunction "1_1") (pintype "passive"))
      (node (ref "R40") (pin "1") (pinfunction "1_1") (pintype "passive"))
      (node (ref "U7") (pin "41") (pinfunction "PC9_41") (pintype "bidirectional"))
    )
    (net (code "64") (name "Net-(U7-VDDA)") (class "Default")
      (node (ref "C21") (pin "1") (pinfunction "1_1") (pintype "passive"))
      (node (ref "C4") (pin "1") (pinfunction "1_1") (pintype "passive"))
      (node (ref "L1") (pin "1") (pinfunction "1_1") (pintype "passive"))
      (node (ref "U7") (pin "29") (pinfunction "VDDA_29") (pintype "power_in"))
    )
    (net (code "65") (name "Net-(U7-VREF+)") (class "Default")
      (node (ref "C18") (pin "1") (pinfunction "1_1") (pintype "passive"))
      (node (ref "C19") (pin "1") (pinfunction "1_1") (pintype "passive"))
      (node (ref "L2") (pin "1") (pinfunction "1_1") (pintype "passive"))
      (node (ref "U7") (pin "28") (pinfunction "VREF+_28") (pintype "power_in"))
    )
    (net (code "66") (name "PHASE_A") (class "Default")
      (node (ref "C7") (pin "2") (pinfunction "2_2") (pintype "passive"))
      (node (ref "MOTOR") (pin "3") (pinfunction "KL_3") (pintype "passive"))
      (node (ref "Q1") (pin "3") (pinfunction "S_3") (pintype "passive"))
      (node (ref "Q2") (pin "2") (pinfunction "D_2") (pintype "passive"))
      (node (ref "R20") (pin "2") (pinfunction "2_2") (pintype "passive"))
      (node (ref "U$1") (pin "6") (pinfunction "VS_6") (pintype "bidirectional"))
    )
    (net (code "67") (name "PHASE_B") (class "Default")
      (node (ref "C9") (pin "2") (pinfunction "2_2") (pintype "passive"))
      (node (ref "MOTOR") (pin "2") (pinfunction "KL_2") (pintype "passive"))
      (node (ref "Q3") (pin "3") (pinfunction "S_3") (pintype "passive"))
      (node (ref "Q4") (pin "2") (pinfunction "D_2") (pintype "passive"))
      (node (ref "R18") (pin "2") (pinfunction "2_2") (pintype "passive"))
      (node (ref "U$2") (pin "6") (pinfunction "VS_6") (pintype "bidirectional"))
    )
    (net (code "68") (name "PHASE_C") (class "Default")
      (node (ref "C10") (pin "2") (pinfunction "2_2") (pintype "passive"))
      (node (ref "MOTOR") (pin "1") (pinfunction "KL_1") (pintype "passive"))
      (node (ref "Q5") (pin "3") (pinfunction "S_3") (pintype "passive"))
      (node (ref "Q6") (pin "2") (pinfunction "D_2") (pintype "passive"))
      (node (ref "R16") (pin "2") (pinfunction "2_2") (pintype "passive"))
      (node (ref "U$3") (pin "6") (pinfunction "VS_6") (pintype "bidirectional"))
    )
    (net (code "69") (name "RESET") (class "Default")
      (node (ref "C20") (pin "1") (pinfunction "1_1") (pintype "passive"))
      (node (ref "D4") (pin "1") (pinfunction "K_1") (pintype "passive"))
      (node (ref "R1") (pin "1") (pinfunction "1_1") (pintype "passive"))
      (node (ref "S1") (pin "1") (pinfunction "1_1") (pintype "passive"))
      (node (ref "S1") (pin "2") (pinfunction "2_2") (pintype "passive"))
      (node (ref "STLINK") (pin "4") (pinfunction "4_4") (pintype "passive"))
      (node (ref "U7") (pin "7") (pinfunction "PG10-~{RST}_7") (pintype "bidirectional"))
    )
    (net (code "70") (name "SWCLK") (class "Default")
      (node (ref "STLINK") (pin "3") (pinfunction "3_3") (pintype "passive"))
      (node (ref "U7") (pin "50") (pinfunction "PA14_50") (pintype "bidirectional"))
    )
    (net (code "71") (name "SWDIO") (class "Default")
      (node (ref "STLINK") (pin "2") (pinfunction "2_2") (pintype "passive"))
      (node (ref "U7") (pin "49") (pinfunction "PA13_49") (pintype "bidirectional"))
    )
    (net (code "72") (name "TTL_RX") (class "Default")
      (node (ref "U7") (pin "52") (pinfunction "PC10_52") (pintype "bidirectional"))
      (node (ref "USB-TTL") (pin "2") (pinfunction "2_2") (pintype "passive"))
    )
    (net (code "73") (name "TTL_TX") (class "Default")
      (node (ref "U7") (pin "53") (pinfunction "PC11_53") (pintype "bidirectional"))
      (node (ref "USB-TTL") (pin "3") (pinfunction "3_3") (pintype "passive"))
    )
    (net (code "74") (name "VIN(-)") (class "Default")
      (node (ref "R3") (pin "2") (pinfunction "2_2") (pintype "passive"))
      (node (ref "RSHUNT") (pin "1") (pinfunction "1_1") (pintype "passive"))
      (node (ref "VIN") (pin "2") (pinfunction "KL_2") (pintype "passive"))
    )
    (net (code "75") (name "VIRTUAL_GND") (class "Default")
      (node (ref "R13") (pin "1") (pinfunction "1_1") (pintype "passive"))
      (node (ref "R14") (pin "1") (pinfunction "1_1") (pintype "passive"))
      (node (ref "R15") (pin "1") (pinfunction "1_1") (pintype "passive"))
      (node (ref "U7") (pin "19") (pinfunction "PA5_19") (pintype "bidirectional"))
      (node (ref "U7") (pin "26") (pinfunction "PB2_26") (pintype "bidirectional"))
      (node (ref "U7") (pin "30") (pinfunction "PB10_30") (pintype "bidirectional"))
    )
    (net (code "76") (name "unconnected-(U$4-VREF-Pad5)") (class "Default")
      (node (ref "U$4") (pin "5") (pinfunction "VREF_5") (pintype "output"))
    )
    (net (code "77") (name "unconnected-(U7-PA4-Pad18)") (class "Default")
      (node (ref "U7") (pin "18") (pinfunction "PA4_18") (pintype "bidirectional"))
    )
    (net (code "78") (name "unconnected-(U7-PA6-Pad20)") (class "Default")
      (node (ref "U7") (pin "20") (pinfunction "PA6_20") (pintype "bidirectional"))
    )
    (net (code "79") (name "unconnected-(U7-PA10-Pad44)") (class "Default")
      (node (ref "U7") (pin "44") (pinfunction "PA10_44") (pintype "bidirectional"))
    )
    (net (code "80") (name "unconnected-(U7-PA15-Pad51)") (class "Default")
      (node (ref "U7") (pin "51") (pinfunction "PA15_51") (pintype "bidirectional"))
    )
    (net (code "81") (name "unconnected-(U7-PB1-Pad25)") (class "Default")
      (node (ref "U7") (pin "25") (pinfunction "PB1_25") (pintype "bidirectional"))
    )
    (net (code "82") (name "unconnected-(U7-PB3-Pad56)") (class "Default")
      (node (ref "U7") (pin "56") (pinfunction "PB3_56") (pintype "bidirectional"))
    )
    (net (code "83") (name "unconnected-(U7-PB4-Pad57)") (class "Default")
      (node (ref "U7") (pin "57") (pinfunction "PB4_57") (pintype "bidirectional"))
    )
    (net (code "84") (name "unconnected-(U7-PB5-Pad58)") (class "Default")
      (node (ref "U7") (pin "58") (pinfunction "PB5_58") (pintype "bidirectional"))
    )
    (net (code "85") (name "unconnected-(U7-PB6-Pad59)") (class "Default")
      (node (ref "U7") (pin "59") (pinfunction "PB6_59") (pintype "bidirectional"))
    )
    (net (code "86") (name "unconnected-(U7-PB7-Pad60)") (class "Default")
      (node (ref "U7") (pin "60") (pinfunction "PB7_60") (pintype "bidirectional"))
    )
    (net (code "87") (name "unconnected-(U7-PB9-Pad62)") (class "Default")
      (node (ref "U7") (pin "62") (pinfunction "PB9_62") (pintype "bidirectional"))
    )
    (net (code "88") (name "unconnected-(U7-PB14-Pad36)") (class "Default")
      (node (ref "U7") (pin "36") (pinfunction "PB14_36") (pintype "bidirectional"))
    )
    (net (code "89") (name "unconnected-(U7-PB15-Pad37)") (class "Default")
      (node (ref "U7") (pin "37") (pinfunction "PB15_37") (pintype "bidirectional"))
    )
    (net (code "90") (name "unconnected-(U7-PC3-Pad11)") (class "Default")
      (node (ref "U7") (pin "11") (pinfunction "PC3_11") (pintype "bidirectional"))
    )
    (net (code "91") (name "unconnected-(U7-PC4-Pad22)") (class "Default")
      (node (ref "U7") (pin "22") (pinfunction "PC4_22") (pintype "bidirectional"))
    )
    (net (code "92") (name "unconnected-(U7-PC5-Pad23)") (class "Default")
      (node (ref "U7") (pin "23") (pinfunction "PC5_23") (pintype "bidirectional"))
    )
    (net (code "93") (name "unconnected-(U7-PC6-Pad38)") (class "Default")
      (node (ref "U7") (pin "38") (pinfunction "PC6_38") (pintype "bidirectional"))
    )
    (net (code "94") (name "unconnected-(U7-PC7-Pad39)") (class "Default")
      (node (ref "U7") (pin "39") (pinfunction "PC7_39") (pintype "bidirectional"))
    )
    (net (code "95") (name "unconnected-(U7-PC8-Pad40)") (class "Default")
      (node (ref "U7") (pin "40") (pinfunction "PC8_40") (pintype "bidirectional"))
    )
    (net (code "96") (name "unconnected-(U7-PC12-Pad54)") (class "Default")
      (node (ref "U7") (pin "54") (pinfunction "PC12_54") (pintype "bidirectional"))
    )
    (net (code "97") (name "unconnected-(U7-PC13-Pad2)") (class "Default")
      (node (ref "U7") (pin "2") (pinfunction "PC13_2") (pintype "bidirectional"))
    )
    (net (code "98") (name "unconnected-(U7-PC14-OSC32_IN-Pad3)") (class "Default")
      (node (ref "U7") (pin "3") (pinfunction "PC14-OSC32_IN_3") (pintype "bidirectional"))
    )
    (net (code "99") (name "unconnected-(U7-PD2-Pad55)") (class "Default")
      (node (ref "U7") (pin "55") (pinfunction "PD2_55") (pintype "bidirectional"))
    )
    (net (code "100") (name "unconnected-(U7-PF0-OSC_IN-Pad5)") (class "Default")
      (node (ref "U7") (pin "5") (pinfunction "PF0-OSC_IN_5") (pintype "bidirectional"))
    )
    (net (code "101") (name "unconnected-(U7-PF1-OSC_OUT-Pad6)") (class "Default")
      (node (ref "U7") (pin "6") (pinfunction "PF1-OSC_OUT_6") (pintype "bidirectional"))
    )
  )
)
